# MainBoard_PSU.net
KiCad netlist of a schematic drawn in Altium Designer
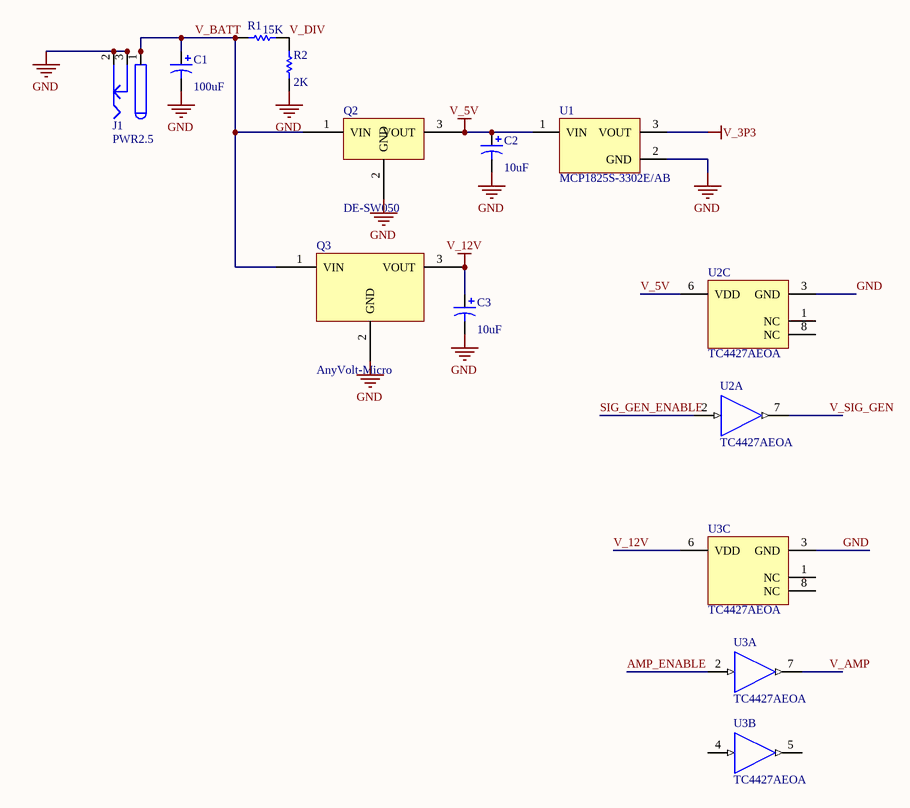
[diagram p0: MainBoard_PSU.SchDoc]

(export (version "E")
  (design (tool "Eeschema 10.0.6"))
  (components
    (comp (ref "C1")
      (value "100uF")
      (footprint "CAPPR2-5x6.8")
      (description "Polarized Capacitor (Radial)")
      (fields (field (name "Comment") "Cap Pol1") (field (name "PUBLISHER") "Altium Limited"))
      (libsource (lib "Miscellaneous Devices") (part "Cap Pol1"))
    )
    (comp (ref "C2")
      (value "10uF")
      (footprint "CAPPR2-5x6.8")
      (description "Polarized Capacitor (Radial)")
      (fields (field (name "Comment") "Cap Pol1") (field (name "PUBLISHER") "Altium Limited"))
      (libsource (lib "Miscellaneous Devices") (part "Cap Pol1"))
    )
    (comp (ref "C3")
      (value "10uF")
      (footprint "CAPPR2-5x6.8")
      (description "Polarized Capacitor (Radial)")
      (fields (field (name "Comment") "Cap Pol1") (field (name "PUBLISHER") "Altium Limited"))
      (libsource (lib "Miscellaneous Devices") (part "Cap Pol1"))
    )
    (comp (ref "J1")
      (value "PWR2.5")
      (footprint "KLD-0202")
      (description "Low Voltage Power Supply Connector")
      (fields (field (name "PUBLISHER") "Altium Limited"))
      (libsource (lib "Miscellaneous Connectors") (part "PWR2.5"))
    )
    (comp (ref "Q2")
      (value "DE-SW050")
      (footprint "TO-220")
      (libsource (lib "MainBoard_Lib") (part "DE-SW050"))
    )
    (comp (ref "Q3")
      (value "AnyVolt-Micro")
      (footprint "TO-220")
      (libsource (lib "MainBoard_Lib") (part "AnyVolt-Micro"))
    )
    (comp (ref "R1")
      (value "15K")
      (footprint "AXIAL-0.3")
      (description "Resistor")
      (fields (field (name "Comment") "Res1") (field (name "PUBLISHER") "Altium Limited"))
      (libsource (lib "Miscellaneous Devices") (part "Res1"))
    )
    (comp (ref "R2")
      (value "2K")
      (footprint "AXIAL-0.3")
      (description "Resistor")
      (fields (field (name "Comment") "Res1") (field (name "PUBLISHER") "Altium Limited"))
      (libsource (lib "Miscellaneous Devices") (part "Res1"))
    )
    (comp (ref "U1")
      (value "MCP1825S-3302E/AB")
      (footprint "TO-220-AB3")
      (description "500 mA, Low Voltage, Low Quiescent Current LDO Regulator, 3-Pin TO-220, Extended Temperature")
      (fields (field (name "PUBLISHER") "Altium Limited"))
      (libsource (lib "Microchip Power Mgt Line Regulator") (part "MCP1825S-3302E/AB"))
    )
    (comp (ref "U2")
      (value "TC4427AEOA")
      (footprint "SOIC-OA8_N")
      (description "1.5A Dual High-Speed Power MOSFET Driver, Non-Inverting, Industrial Temperature")
      (fields (field (name "PUBLISHER") "Altium Limited"))
      (libsource (lib "Microchip Power Mgt MOSFET Driver") (part "TC4427AEOA"))
    )
    (comp (ref "U3")
      (value "TC4427AEOA")
      (footprint "SOIC-OA8_N")
      (description "1.5A Dual High-Speed Power MOSFET Driver, Non-Inverting, Industrial Temperature")
      (fields (field (name "PUBLISHER") "Altium Limited"))
      (libsource (lib "Microchip Power Mgt MOSFET Driver") (part "TC4427AEOA"))
    )
  )
  (nets
    (net (code "1") (name "/AMP_ENABLE") (class "Default")
      (node (ref "U3") (pin "2") (pinfunction "INA_2") (pintype "input"))
    )
    (net (code "2") (name "/SIG_GEN_ENABLE") (class "Default")
      (node (ref "U2") (pin "2") (pinfunction "INA_2") (pintype "input"))
    )
    (net (code "3") (name "/V_AMP") (class "Default")
      (node (ref "U3") (pin "7") (pinfunction "OUTA_7") (pintype "output"))
    )
    (net (code "4") (name "/V_BATT") (class "Default")
      (node (ref "C1") (pin "1") (pinfunction "1_1") (pintype "passive"))
      (node (ref "J1") (pin "1") (pinfunction "1_1") (pintype "power_in"))
      (node (ref "J1") (pin "1A") (pinfunction "1A_1A") (pintype "power_in"))
      (node (ref "J1") (pin "1B") (pinfunction "1B_1B") (pintype "power_in"))
      (node (ref "Q2") (pin "1") (pinfunction "VIN_1") (pintype "power_in"))
      (node (ref "Q3") (pin "1") (pinfunction "VIN_1") (pintype "power_in"))
      (node (ref "R1") (pin "1") (pinfunction "1_1") (pintype "passive"))
    )
    (net (code "5") (name "/V_DIV") (class "Default")
      (node (ref "R1") (pin "2") (pinfunction "2_2") (pintype "passive"))
      (node (ref "R2") (pin "2") (pinfunction "2_2") (pintype "passive"))
    )
    (net (code "6") (name "/V_SIG_GEN") (class "Default")
      (node (ref "U2") (pin "7") (pinfunction "OUTA_7") (pintype "output"))
    )
    (net (code "7") (name "GND") (class "Default")
      (node (ref "C1") (pin "2") (pinfunction "2_2") (pintype "passive"))
      (node (ref "C2") (pin "2") (pinfunction "2_2") (pintype "passive"))
      (node (ref "C3") (pin "2") (pinfunction "2_2") (pintype "passive"))
      (node (ref "J1") (pin "2") (pinfunction "2_2") (pintype "power_in"))
      (node (ref "J1") (pin "2A") (pinfunction "2A_2A") (pintype "power_in"))
      (node (ref "J1") (pin "2B") (pinfunction "2B_2B") (pintype "power_in"))
      (node (ref "J1") (pin "3") (pinfunction "3_3") (pintype "power_in"))
      (node (ref "J1") (pin "3A") (pinfunction "3A_3A") (pintype "power_in"))
      (node (ref "J1") (pin "3B") (pinfunction "3B_3B") (pintype "power_in"))
      (node (ref "Q2") (pin "2") (pinfunction "GND_2") (pintype "power_in"))
      (node (ref "Q3") (pin "2") (pinfunction "GND_2") (pintype "power_in"))
      (node (ref "R2") (pin "1") (pinfunction "1_1") (pintype "passive"))
      (node (ref "U1") (pin "2") (pinfunction "GND_2") (pintype "power_in"))
      (node (ref "U2") (pin "3") (pinfunction "GND_3") (pintype "power_in"))
      (node (ref "U3") (pin "3") (pinfunction "GND_3") (pintype "power_in"))
    )
    (net (code "8") (name "V_3P3") (class "Default")
      (node (ref "U1") (pin "3") (pinfunction "VOUT_3") (pintype "power_in"))
    )
    (net (code "9") (name "V_5V") (class "Default")
      (node (ref "C2") (pin "1") (pinfunction "1_1") (pintype "passive"))
      (node (ref "Q2") (pin "3") (pinfunction "VOUT_3") (pintype "power_in"))
      (node (ref "U1") (pin "1") (pinfunction "VIN_1") (pintype "power_in"))
      (node (ref "U2") (pin "6") (pinfunction "VDD_6") (pintype "power_in"))
    )
    (net (code "10") (name "V_12V") (class "Default")
      (node (ref "C3") (pin "1") (pinfunction "1_1") (pintype "passive"))
      (node (ref "Q3") (pin "3") (pinfunction "VOUT_3") (pintype "power_in"))
      (node (ref "U3") (pin "6") (pinfunction "VDD_6") (pintype "power_in"))
    )
    (net (code "11") (name "unconnected-(U2C-NC-Pad1)") (class "Default")
      (node (ref "U2") (pin "1") (pinfunction "NC_1") (pintype "passive"))
    )
    (net (code "12") (name "unconnected-(U2C-NC-Pad8)") (class "Default")
      (node (ref "U2") (pin "8") (pinfunction "NC_8") (pintype "passive"))
    )
    (net (code "13") (name "unconnected-(U3B-INB-Pad4)") (class "Default")
      (node (ref "U3") (pin "4") (pinfunction "INB_4") (pintype "input"))
    )
    (net (code "14") (name "unconnected-(U3B-OUTB-Pad5)") (class "Default")
      (node (ref "U3") (pin "5") (pinfunction "OUTB_5") (pintype "output"))
    )
    (net (code "15") (name "unconnected-(U3C-NC-Pad1)") (class "Default")
      (node (ref "U3") (pin "1") (pinfunction "NC_1") (pintype "passive"))
    )
    (net (code "16") (name "unconnected-(U3C-NC-Pad8)") (class "Default")
      (node (ref "U3") (pin "8") (pinfunction "NC_8") (pintype "passive"))
    )
  )
)
